# USB2UART.net
KiCad netlist of a schematic drawn in Altium Designer
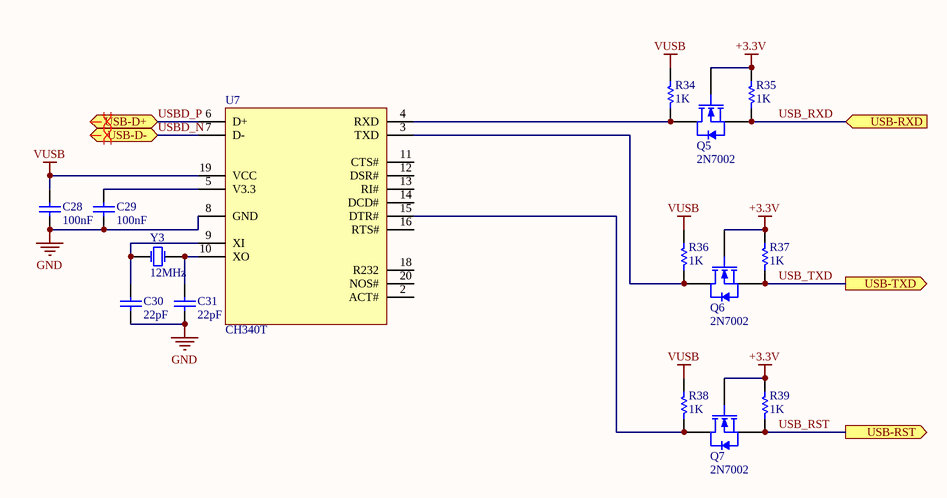
[diagram p0: USB2UART.SchDoc]

(export (version "E")
  (design (tool "Eeschema 10.0.6"))
  (components
    (comp (ref "C28")
      (value "100nF")
      (footprint "C603")
      (description "Capacitor")
      (fields (field (name "DESIGNER") "Parsa Malekpour"))
      (libsource (lib "UserPKG") (part "Cap"))
    )
    (comp (ref "C29")
      (value "100nF")
      (footprint "C603")
      (description "Capacitor")
      (fields (field (name "DESIGNER") "Parsa Malekpour"))
      (libsource (lib "UserPKG") (part "Cap"))
    )
    (comp (ref "C30")
      (value "22pF")
      (footprint "C603")
      (description "Capacitor")
      (fields (field (name "DESIGNER") "Parsa Malekpour"))
      (libsource (lib "UserPKG") (part "Cap"))
    )
    (comp (ref "C31")
      (value "22pF")
      (footprint "C603")
      (description "Capacitor")
      (fields (field (name "DESIGNER") "Parsa Malekpour"))
      (libsource (lib "UserPKG") (part "Cap"))
    )
    (comp (ref "Q5")
      (value "2N7002")
      (footprint "SOT-23")
      (description "N-channel Enhancement Mode Field-effect Transistor")
      (fields (field (name "PUBLISHER") "Altium Limited"))
      (libsource (lib "Philips Discrete MOSFET - Low Power") (part "2N7002"))
    )
    (comp (ref "Q6")
      (value "2N7002")
      (footprint "SOT-23")
      (description "N-channel Enhancement Mode Field-effect Transistor")
      (fields (field (name "PUBLISHER") "Altium Limited"))
      (libsource (lib "Philips Discrete MOSFET - Low Power") (part "2N7002"))
    )
    (comp (ref "Q7")
      (value "2N7002")
      (footprint "SOT-23")
      (description "N-channel Enhancement Mode Field-effect Transistor")
      (fields (field (name "PUBLISHER") "Altium Limited"))
      (libsource (lib "Philips Discrete MOSFET - Low Power") (part "2N7002"))
    )
    (comp (ref "R34")
      (value "1K")
      (footprint "R0603")
      (description "Resistor")
      (fields (field (name "DESIGNER") "Parsa Malekpour"))
      (libsource (lib "UserPKG") (part "RES"))
    )
    (comp (ref "R35")
      (value "1K")
      (footprint "R0603")
      (description "Resistor")
      (fields (field (name "DESIGNER") "Parsa Malekpour"))
      (libsource (lib "UserPKG") (part "RES"))
    )
    (comp (ref "R36")
      (value "1K")
      (footprint "R0603")
      (description "Resistor")
      (fields (field (name "DESIGNER") "Parsa Malekpour"))
      (libsource (lib "UserPKG") (part "RES"))
    )
    (comp (ref "R37")
      (value "1K")
      (footprint "R0603")
      (description "Resistor")
      (fields (field (name "DESIGNER") "Parsa Malekpour"))
      (libsource (lib "UserPKG") (part "RES"))
    )
    (comp (ref "R38")
      (value "1K")
      (footprint "R0603")
      (description "Resistor")
      (fields (field (name "DESIGNER") "Parsa Malekpour"))
      (libsource (lib "UserPKG") (part "RES"))
    )
    (comp (ref "R39")
      (value "1K")
      (footprint "R0603")
      (description "Resistor")
      (fields (field (name "DESIGNER") "Parsa Malekpour"))
      (libsource (lib "UserPKG") (part "RES"))
    )
    (comp (ref "U7")
      (value "CH340T")
      (footprint "SSOP-20n")
      (description "USB Bus Convert Chip and It Can Realize USB Convert to Serial Interface")
      (libsource (lib "UserPKG") (part "CH340T"))
    )
    (comp (ref "Y3")
      (value "12MHz")
      (footprint "XTAL-SMD")
      (description "Crystal Oscillator")
      (fields (field (name "DESIGNER") "Parsa Malekpour") (field (name "EMAIL") "Malekpour.parsa@Gmail.com"))
      (libsource (lib "UserPKG") (part "XTAL"))
    )
  )
  (nets
    (net (code "1") (name "+3.3V") (class "Default")
      (node (ref "Q5") (pin "1") (pinfunction "G_1") (pintype "passive"))
      (node (ref "Q6") (pin "1") (pinfunction "G_1") (pintype "passive"))
      (node (ref "Q7") (pin "1") (pinfunction "G_1") (pintype "passive"))
      (node (ref "R35") (pin "2") (pinfunction "2_2") (pintype "passive"))
      (node (ref "R37") (pin "2") (pinfunction "2_2") (pintype "passive"))
      (node (ref "R39") (pin "2") (pinfunction "2_2") (pintype "passive"))
    )
    (net (code "2") (name "/USBD_N") (class "Default")
      (node (ref "U7") (pin "7") (pinfunction "D-_7") (pintype "passive"))
    )
    (net (code "3") (name "/USBD_P") (class "Default")
      (node (ref "U7") (pin "6") (pinfunction "D+_6") (pintype "passive"))
    )
    (net (code "4") (name "/USB_RST") (class "Default")
      (node (ref "Q7") (pin "2") (pinfunction "S_2") (pintype "passive"))
      (node (ref "R39") (pin "1") (pinfunction "1_1") (pintype "passive"))
    )
    (net (code "5") (name "/USB_RXD") (class "Default")
      (node (ref "Q5") (pin "2") (pinfunction "S_2") (pintype "passive"))
      (node (ref "R35") (pin "1") (pinfunction "1_1") (pintype "passive"))
    )
    (net (code "6") (name "/USB_TXD") (class "Default")
      (node (ref "Q6") (pin "2") (pinfunction "S_2") (pintype "passive"))
      (node (ref "R37") (pin "1") (pinfunction "1_1") (pintype "passive"))
    )
    (net (code "7") (name "GND") (class "Default")
      (node (ref "C28") (pin "1") (pinfunction "1_1") (pintype "passive"))
      (node (ref "C29") (pin "1") (pinfunction "1_1") (pintype "passive"))
      (node (ref "C30") (pin "1") (pinfunction "1_1") (pintype "passive"))
      (node (ref "C31") (pin "1") (pinfunction "1_1") (pintype "passive"))
      (node (ref "U7") (pin "8") (pinfunction "GND_8") (pintype "passive"))
    )
    (net (code "8") (name "Net-(Q5-D)") (class "Default")
      (node (ref "Q5") (pin "3") (pinfunction "D_3") (pintype "passive"))
      (node (ref "R34") (pin "1") (pinfunction "1_1") (pintype "passive"))
      (node (ref "U7") (pin "4") (pinfunction "RXD_4") (pintype "passive"))
    )
    (net (code "9") (name "Net-(Q6-D)") (class "Default")
      (node (ref "Q6") (pin "3") (pinfunction "D_3") (pintype "passive"))
      (node (ref "R36") (pin "1") (pinfunction "1_1") (pintype "passive"))
      (node (ref "U7") (pin "3") (pinfunction "TXD_3") (pintype "passive"))
    )
    (net (code "10") (name "Net-(Q7-D)") (class "Default")
      (node (ref "Q7") (pin "3") (pinfunction "D_3") (pintype "passive"))
      (node (ref "R38") (pin "1") (pinfunction "1_1") (pintype "passive"))
      (node (ref "U7") (pin "15") (pinfunction "DTR#_15") (pintype "passive"))
    )
    (net (code "11") (name "Net-(U7-V3.3)") (class "Default")
      (node (ref "C29") (pin "2") (pinfunction "2_2") (pintype "passive"))
      (node (ref "U7") (pin "5") (pinfunction "V3.3_5") (pintype "passive"))
    )
    (net (code "12") (name "Net-(U7-XI)") (class "Default")
      (node (ref "C30") (pin "2") (pinfunction "2_2") (pintype "passive"))
      (node (ref "U7") (pin "9") (pinfunction "XI_9") (pintype "passive"))
      (node (ref "Y3") (pin "1") (pinfunction "OSC1_1") (pintype "passive"))
    )
    (net (code "13") (name "Net-(U7-XO)") (class "Default")
      (node (ref "C31") (pin "2") (pinfunction "2_2") (pintype "passive"))
      (node (ref "U7") (pin "10") (pinfunction "XO_10") (pintype "passive"))
      (node (ref "Y3") (pin "2") (pinfunction "OSC2_2") (pintype "passive"))
    )
    (net (code "14") (name "VUSB") (class "Default")
      (node (ref "C28") (pin "2") (pinfunction "2_2") (pintype "passive"))
      (node (ref "R34") (pin "2") (pinfunction "2_2") (pintype "passive"))
      (node (ref "R36") (pin "2") (pinfunction "2_2") (pintype "passive"))
      (node (ref "R38") (pin "2") (pinfunction "2_2") (pintype "passive"))
      (node (ref "U7") (pin "19") (pinfunction "VCC_19") (pintype "passive"))
    )
    (net (code "15") (name "unconnected-(U7-ACT#-Pad2)") (class "Default")
      (node (ref "U7") (pin "2") (pinfunction "ACT#_2") (pintype "passive"))
    )
    (net (code "16") (name "unconnected-(U7-CKO-Pad1)") (class "Default")
      (node (ref "U7") (pin "1") (pinfunction "CKO_1") (pintype "passive"))
    )
    (net (code "17") (name "unconnected-(U7-CTS#-Pad11)") (class "Default")
      (node (ref "U7") (pin "11") (pinfunction "CTS#_11") (pintype "passive"))
    )
    (net (code "18") (name "unconnected-(U7-DCD#-Pad14)") (class "Default")
      (node (ref "U7") (pin "14") (pinfunction "DCD#_14") (pintype "passive"))
    )
    (net (code "19") (name "unconnected-(U7-DSR#-Pad12)") (class "Default")
      (node (ref "U7") (pin "12") (pinfunction "DSR#_12") (pintype "passive"))
    )
    (net (code "20") (name "unconnected-(U7-IR#-Pad17)") (class "Default")
      (node (ref "U7") (pin "17") (pinfunction "IR#_17") (pintype "passive"))
    )
    (net (code "21") (name "unconnected-(U7-NOS#-Pad20)") (class "Default")
      (node (ref "U7") (pin "20") (pinfunction "NOS#_20") (pintype "passive"))
    )
    (net (code "22") (name "unconnected-(U7-R232-Pad18)") (class "Default")
      (node (ref "U7") (pin "18") (pinfunction "R232_18") (pintype "passive"))
    )
    (net (code "23") (name "unconnected-(U7-RI#-Pad13)") (class "Default")
      (node (ref "U7") (pin "13") (pinfunction "RI#_13") (pintype "passive"))
    )
    (net (code "24") (name "unconnected-(U7-RTS#-Pad16)") (class "Default")
      (node (ref "U7") (pin "16") (pinfunction "RTS#_16") (pintype "passive"))
    )
  )
)
